# OUT_7SEG.net
KiCad netlist of a schematic drawn in EAGLE
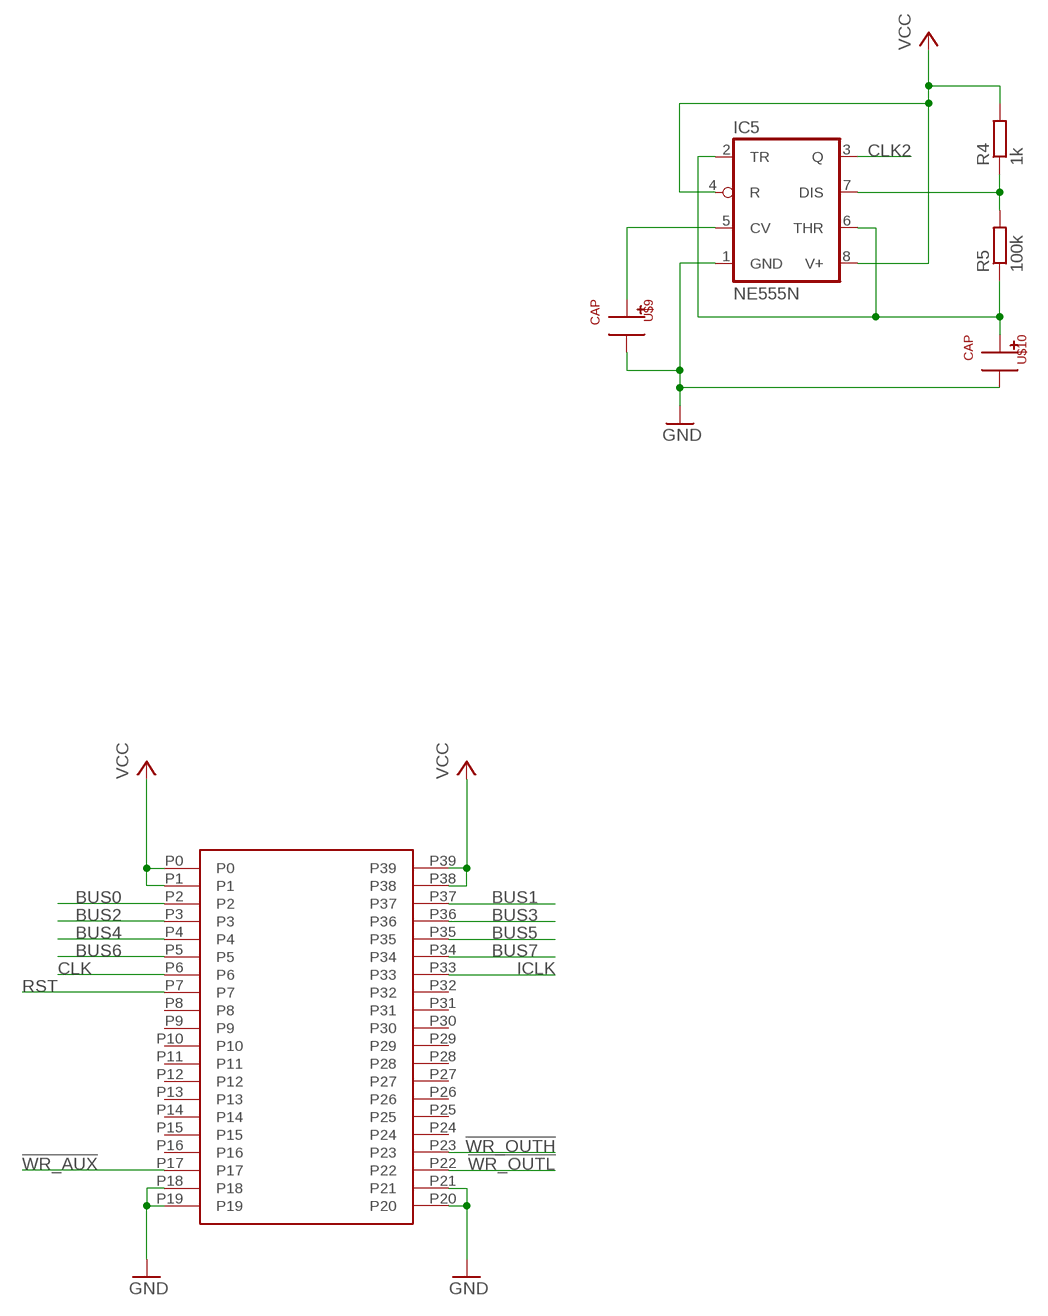
[diagram p0: schematic, sheet 1, part 1 of 2]
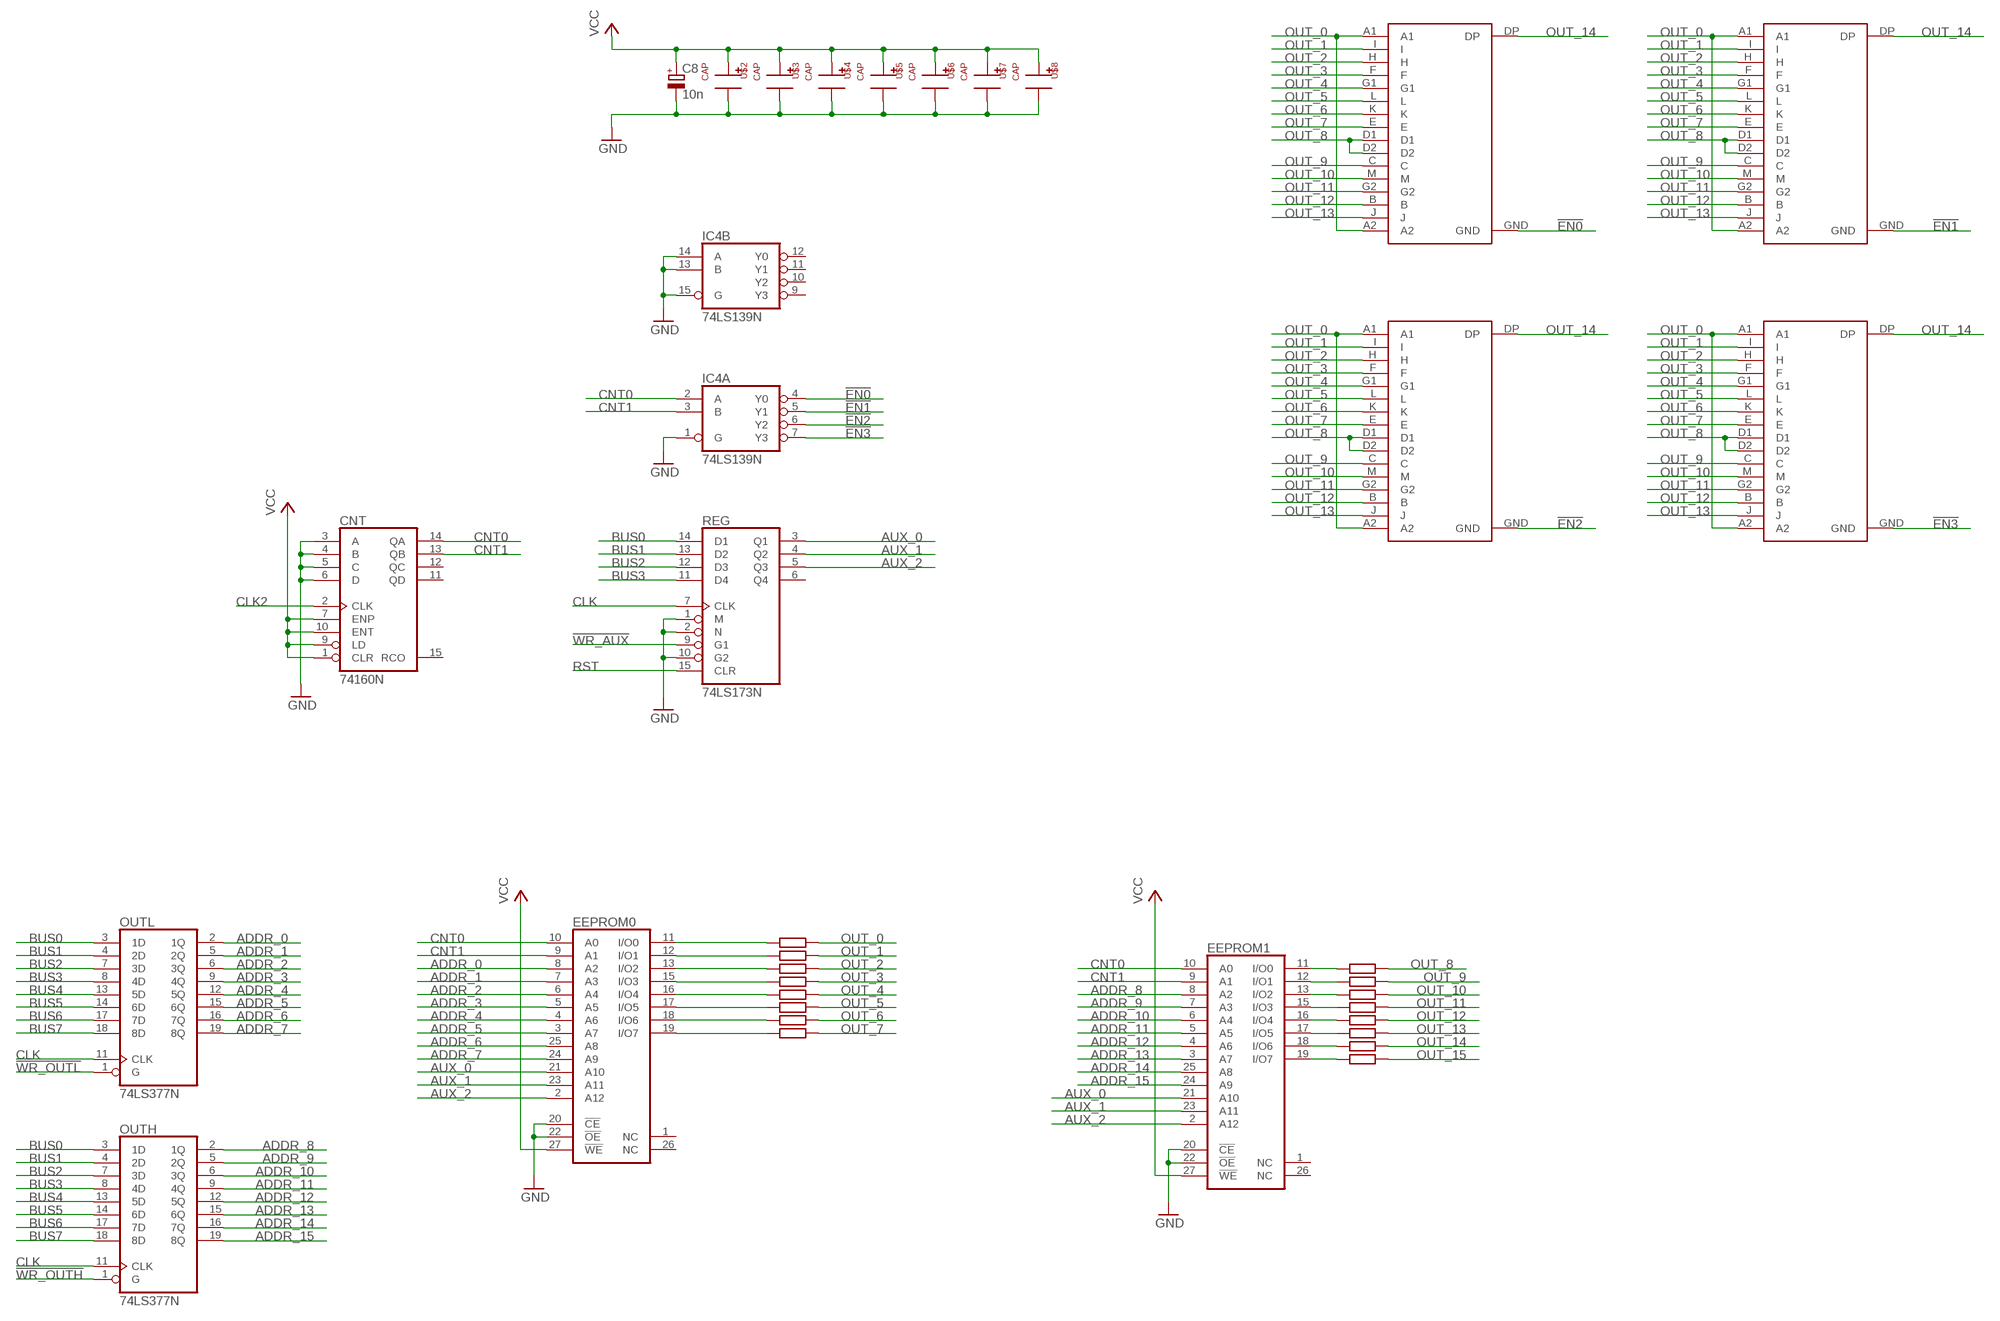
[diagram p1: schematic, sheet 1, part 2 of 2]

(export (version "E")
  (design (tool "Eeschema 10.0.6"))
  (components
    (comp (ref "C8")
      (value "10n")
      (footprint "eagle-import:E2,5-6E")
      (libsource (lib "eagle-import") (part "CPOL-EUE2,5-6E"))
    )
    (comp (ref "CNT")
      (value "74160N")
      (footprint "eagle-import:DIL16")
      (libsource (lib "eagle-import") (part "74160N"))
    )
    (comp (ref "DISP1")
      (value "16SEG")
      (footprint "eagle-import:16SEG")
      (libsource (lib "eagle-import") (part "16SEG"))
    )
    (comp (ref "DISP2")
      (value "16SEG")
      (footprint "eagle-import:16SEG")
      (libsource (lib "eagle-import") (part "16SEG"))
    )
    (comp (ref "DISP3")
      (value "16SEG")
      (footprint "eagle-import:16SEG")
      (libsource (lib "eagle-import") (part "16SEG"))
    )
    (comp (ref "DISP4")
      (value "16SEG")
      (footprint "eagle-import:16SEG")
      (libsource (lib "eagle-import") (part "16SEG"))
    )
    (comp (ref "EEPROM0")
      (value "78C64P")
      (footprint "eagle-import:DIL28-6")
      (libsource (lib "eagle-import") (part "78C64P"))
    )
    (comp (ref "EEPROM1")
      (value "78C64P")
      (footprint "eagle-import:DIL28-6")
      (libsource (lib "eagle-import") (part "78C64P"))
    )
    (comp (ref "IC4")
      (value "74LS139N")
      (footprint "eagle-import:DIL16")
      (libsource (lib "eagle-import") (part "74139NLS"))
    )
    (comp (ref "IC5")
      (value "NE555N")
      (footprint "eagle-import:DIL08")
      (libsource (lib "eagle-import") (part "555NNE"))
    )
    (comp (ref "OUTH")
      (value "74LS377N")
      (footprint "eagle-import:DIL20")
      (libsource (lib "eagle-import") (part "74377NLS"))
    )
    (comp (ref "OUTL")
      (value "74LS377N")
      (footprint "eagle-import:DIL20")
      (libsource (lib "eagle-import") (part "74377NLS"))
    )
    (comp (ref "R1")
      (value "330")
      (footprint "eagle-import:R0805")
      (libsource (lib "eagle-import") (part "R-EU_R0805"))
    )
    (comp (ref "R2")
      (value "330")
      (footprint "eagle-import:R0805")
      (libsource (lib "eagle-import") (part "R-EU_R0805"))
    )
    (comp (ref "R3")
      (value "330")
      (footprint "eagle-import:R0805")
      (libsource (lib "eagle-import") (part "R-EU_R0805"))
    )
    (comp (ref "R4")
      (value "1k")
      (footprint "eagle-import:0204_7")
      (libsource (lib "eagle-import") (part "R-EU_0204/7"))
    )
    (comp (ref "R5")
      (value "100k")
      (footprint "eagle-import:0204_7")
      (libsource (lib "eagle-import") (part "R-EU_0204/7"))
    )
    (comp (ref "R6")
      (value "330")
      (footprint "eagle-import:R0805")
      (libsource (lib "eagle-import") (part "R-EU_R0805"))
    )
    (comp (ref "R7")
      (value "330")
      (footprint "eagle-import:R0805")
      (libsource (lib "eagle-import") (part "R-EU_R0805"))
    )
    (comp (ref "R8")
      (value "330")
      (footprint "eagle-import:R0805")
      (libsource (lib "eagle-import") (part "R-EU_R0805"))
    )
    (comp (ref "R9")
      (value "330")
      (footprint "eagle-import:R0805")
      (libsource (lib "eagle-import") (part "R-EU_R0805"))
    )
    (comp (ref "R10")
      (value "330")
      (footprint "eagle-import:R0805")
      (libsource (lib "eagle-import") (part "R-EU_R0805"))
    )
    (comp (ref "R11")
      (value "330")
      (footprint "eagle-import:R0805")
      (libsource (lib "eagle-import") (part "R-EU_R0805"))
    )
    (comp (ref "R12")
      (value "330")
      (footprint "eagle-import:R0805")
      (libsource (lib "eagle-import") (part "R-EU_R0805"))
    )
    (comp (ref "R13")
      (value "330")
      (footprint "eagle-import:R0805")
      (libsource (lib "eagle-import") (part "R-EU_R0805"))
    )
    (comp (ref "R14")
      (value "330")
      (footprint "eagle-import:R0805")
      (libsource (lib "eagle-import") (part "R-EU_R0805"))
    )
    (comp (ref "R15")
      (value "330")
      (footprint "eagle-import:R0805")
      (libsource (lib "eagle-import") (part "R-EU_R0805"))
    )
    (comp (ref "R16")
      (value "330")
      (footprint "eagle-import:R0805")
      (libsource (lib "eagle-import") (part "R-EU_R0805"))
    )
    (comp (ref "R17")
      (value "330")
      (footprint "eagle-import:R0805")
      (libsource (lib "eagle-import") (part "R-EU_R0805"))
    )
    (comp (ref "R41")
      (value "330")
      (footprint "eagle-import:R0805")
      (libsource (lib "eagle-import") (part "R-EU_R0805"))
    )
    (comp (ref "REG")
      (value "74LS173N")
      (footprint "eagle-import:DIL16")
      (libsource (lib "eagle-import") (part "74173NLS"))
    )
    (comp (ref "U$1")
      (value "2X40")
      (footprint "eagle-import:2X40")
      (libsource (lib "eagle-import") (part "2X40"))
    )
    (comp (ref "U$2")
      (value "CAP")
      (footprint "eagle-import:CAP")
      (libsource (lib "eagle-import") (part "CAP"))
    )
    (comp (ref "U$3")
      (value "CAP")
      (footprint "eagle-import:CAP")
      (libsource (lib "eagle-import") (part "CAP"))
    )
    (comp (ref "U$4")
      (value "CAP")
      (footprint "eagle-import:CAP")
      (libsource (lib "eagle-import") (part "CAP"))
    )
    (comp (ref "U$5")
      (value "CAP")
      (footprint "eagle-import:CAP")
      (libsource (lib "eagle-import") (part "CAP"))
    )
    (comp (ref "U$6")
      (value "CAP")
      (footprint "eagle-import:CAP")
      (libsource (lib "eagle-import") (part "CAP"))
    )
    (comp (ref "U$7")
      (value "CAP")
      (footprint "eagle-import:CAP")
      (libsource (lib "eagle-import") (part "CAP"))
    )
    (comp (ref "U$8")
      (value "CAP")
      (footprint "eagle-import:CAP")
      (libsource (lib "eagle-import") (part "CAP"))
    )
    (comp (ref "U$9")
      (value "CAP")
      (footprint "eagle-import:CAP")
      (libsource (lib "eagle-import") (part "CAP"))
    )
    (comp (ref "U$10")
      (value "CAP")
      (footprint "eagle-import:CAP")
      (libsource (lib "eagle-import") (part "CAP"))
    )
  )
  (nets
    (net (code "1") (name "/ADDR_0") (class "Default")
      (node (ref "EEPROM0") (pin "8") (pinfunction "A2_8") (pintype "input"))
      (node (ref "OUTL") (pin "2") (pinfunction "1Q_2") (pintype "output"))
    )
    (net (code "2") (name "/ADDR_1") (class "Default")
      (node (ref "EEPROM0") (pin "7") (pinfunction "A3_7") (pintype "input"))
      (node (ref "OUTL") (pin "5") (pinfunction "2Q_5") (pintype "output"))
    )
    (net (code "3") (name "/ADDR_2") (class "Default")
      (node (ref "EEPROM0") (pin "6") (pinfunction "A4_6") (pintype "input"))
      (node (ref "OUTL") (pin "6") (pinfunction "3Q_6") (pintype "output"))
    )
    (net (code "4") (name "/ADDR_3") (class "Default")
      (node (ref "EEPROM0") (pin "5") (pinfunction "A5_5") (pintype "input"))
      (node (ref "OUTL") (pin "9") (pinfunction "4Q_9") (pintype "output"))
    )
    (net (code "5") (name "/ADDR_4") (class "Default")
      (node (ref "EEPROM0") (pin "4") (pinfunction "A6_4") (pintype "input"))
      (node (ref "OUTL") (pin "12") (pinfunction "5Q_12") (pintype "output"))
    )
    (net (code "6") (name "/ADDR_5") (class "Default")
      (node (ref "EEPROM0") (pin "3") (pinfunction "A7_3") (pintype "input"))
      (node (ref "OUTL") (pin "15") (pinfunction "6Q_15") (pintype "output"))
    )
    (net (code "7") (name "/ADDR_6") (class "Default")
      (node (ref "EEPROM0") (pin "25") (pinfunction "A8_25") (pintype "input"))
      (node (ref "OUTL") (pin "16") (pinfunction "7Q_16") (pintype "output"))
    )
    (net (code "8") (name "/ADDR_7") (class "Default")
      (node (ref "EEPROM0") (pin "24") (pinfunction "A9_24") (pintype "input"))
      (node (ref "OUTL") (pin "19") (pinfunction "8Q_19") (pintype "output"))
    )
    (net (code "9") (name "/ADDR_8") (class "Default")
      (node (ref "EEPROM1") (pin "8") (pinfunction "A2_8") (pintype "input"))
      (node (ref "OUTH") (pin "2") (pinfunction "1Q_2") (pintype "output"))
    )
    (net (code "10") (name "/ADDR_9") (class "Default")
      (node (ref "EEPROM1") (pin "7") (pinfunction "A3_7") (pintype "input"))
      (node (ref "OUTH") (pin "5") (pinfunction "2Q_5") (pintype "output"))
    )
    (net (code "11") (name "/ADDR_10") (class "Default")
      (node (ref "EEPROM1") (pin "6") (pinfunction "A4_6") (pintype "input"))
      (node (ref "OUTH") (pin "6") (pinfunction "3Q_6") (pintype "output"))
    )
    (net (code "12") (name "/ADDR_11") (class "Default")
      (node (ref "EEPROM1") (pin "5") (pinfunction "A5_5") (pintype "input"))
      (node (ref "OUTH") (pin "9") (pinfunction "4Q_9") (pintype "output"))
    )
    (net (code "13") (name "/ADDR_12") (class "Default")
      (node (ref "EEPROM1") (pin "4") (pinfunction "A6_4") (pintype "input"))
      (node (ref "OUTH") (pin "12") (pinfunction "5Q_12") (pintype "output"))
    )
    (net (code "14") (name "/ADDR_13") (class "Default")
      (node (ref "EEPROM1") (pin "3") (pinfunction "A7_3") (pintype "input"))
      (node (ref "OUTH") (pin "15") (pinfunction "6Q_15") (pintype "output"))
    )
    (net (code "15") (name "/ADDR_14") (class "Default")
      (node (ref "EEPROM1") (pin "25") (pinfunction "A8_25") (pintype "input"))
      (node (ref "OUTH") (pin "16") (pinfunction "7Q_16") (pintype "output"))
    )
    (net (code "16") (name "/ADDR_15") (class "Default")
      (node (ref "EEPROM1") (pin "24") (pinfunction "A9_24") (pintype "input"))
      (node (ref "OUTH") (pin "19") (pinfunction "8Q_19") (pintype "output"))
    )
    (net (code "17") (name "/AUX_0") (class "Default")
      (node (ref "EEPROM0") (pin "21") (pinfunction "A10_21") (pintype "input"))
      (node (ref "EEPROM1") (pin "21") (pinfunction "A10_21") (pintype "input"))
      (node (ref "REG") (pin "3") (pinfunction "Q1_3") (pintype "tri_state"))
    )
    (net (code "18") (name "/AUX_1") (class "Default")
      (node (ref "EEPROM0") (pin "23") (pinfunction "A11_23") (pintype "input"))
      (node (ref "EEPROM1") (pin "23") (pinfunction "A11_23") (pintype "input"))
      (node (ref "REG") (pin "4") (pinfunction "Q2_4") (pintype "tri_state"))
    )
    (net (code "19") (name "/AUX_2") (class "Default")
      (node (ref "EEPROM0") (pin "2") (pinfunction "A12_2") (pintype "input"))
      (node (ref "EEPROM1") (pin "2") (pinfunction "A12_2") (pintype "input"))
      (node (ref "REG") (pin "5") (pinfunction "Q3_5") (pintype "tri_state"))
    )
    (net (code "20") (name "/BUS0") (class "Default")
      (node (ref "OUTH") (pin "3") (pinfunction "1D_3") (pintype "input"))
      (node (ref "OUTL") (pin "3") (pinfunction "1D_3") (pintype "input"))
      (node (ref "REG") (pin "14") (pinfunction "D1_14") (pintype "input"))
      (node (ref "U$1") (pin "P2") (pinfunction "P2_P2") (pintype "bidirectional"))
    )
    (net (code "21") (name "/BUS1") (class "Default")
      (node (ref "OUTH") (pin "4") (pinfunction "2D_4") (pintype "input"))
      (node (ref "OUTL") (pin "4") (pinfunction "2D_4") (pintype "input"))
      (node (ref "REG") (pin "13") (pinfunction "D2_13") (pintype "input"))
      (node (ref "U$1") (pin "P37") (pinfunction "P37_P37") (pintype "bidirectional"))
    )
    (net (code "22") (name "/BUS2") (class "Default")
      (node (ref "OUTH") (pin "7") (pinfunction "3D_7") (pintype "input"))
      (node (ref "OUTL") (pin "7") (pinfunction "3D_7") (pintype "input"))
      (node (ref "REG") (pin "12") (pinfunction "D3_12") (pintype "input"))
      (node (ref "U$1") (pin "P3") (pinfunction "P3_P3") (pintype "bidirectional"))
    )
    (net (code "23") (name "/BUS3") (class "Default")
      (node (ref "OUTH") (pin "8") (pinfunction "4D_8") (pintype "input"))
      (node (ref "OUTL") (pin "8") (pinfunction "4D_8") (pintype "input"))
      (node (ref "REG") (pin "11") (pinfunction "D4_11") (pintype "input"))
      (node (ref "U$1") (pin "P36") (pinfunction "P36_P36") (pintype "bidirectional"))
    )
    (net (code "24") (name "/BUS4") (class "Default")
      (node (ref "OUTH") (pin "13") (pinfunction "5D_13") (pintype "input"))
      (node (ref "OUTL") (pin "13") (pinfunction "5D_13") (pintype "input"))
      (node (ref "U$1") (pin "P4") (pinfunction "P4_P4") (pintype "bidirectional"))
    )
    (net (code "25") (name "/BUS5") (class "Default")
      (node (ref "OUTH") (pin "14") (pinfunction "6D_14") (pintype "input"))
      (node (ref "OUTL") (pin "14") (pinfunction "6D_14") (pintype "input"))
      (node (ref "U$1") (pin "P35") (pinfunction "P35_P35") (pintype "bidirectional"))
    )
    (net (code "26") (name "/BUS6") (class "Default")
      (node (ref "OUTH") (pin "17") (pinfunction "7D_17") (pintype "input"))
      (node (ref "OUTL") (pin "17") (pinfunction "7D_17") (pintype "input"))
      (node (ref "U$1") (pin "P5") (pinfunction "P5_P5") (pintype "bidirectional"))
    )
    (net (code "27") (name "/BUS7") (class "Default")
      (node (ref "OUTH") (pin "18") (pinfunction "8D_18") (pintype "input"))
      (node (ref "OUTL") (pin "18") (pinfunction "8D_18") (pintype "input"))
      (node (ref "U$1") (pin "P34") (pinfunction "P34_P34") (pintype "bidirectional"))
    )
    (net (code "28") (name "/CLK") (class "Default")
      (node (ref "OUTH") (pin "11") (pinfunction "CLK_11") (pintype "input"))
      (node (ref "OUTL") (pin "11") (pinfunction "CLK_11") (pintype "input"))
      (node (ref "REG") (pin "7") (pinfunction "CLK_7") (pintype "input"))
      (node (ref "U$1") (pin "P6") (pinfunction "P6_P6") (pintype "bidirectional"))
    )
    (net (code "29") (name "/CLK2") (class "Default")
      (node (ref "CNT") (pin "2") (pinfunction "CLK_2") (pintype "input"))
      (node (ref "IC5") (pin "3") (pinfunction "Q_3") (pintype "output"))
    )
    (net (code "30") (name "/CNT0") (class "Default")
      (node (ref "CNT") (pin "14") (pinfunction "QA_14") (pintype "output"))
      (node (ref "EEPROM0") (pin "10") (pinfunction "A0_10") (pintype "input"))
      (node (ref "EEPROM1") (pin "10") (pinfunction "A0_10") (pintype "input"))
      (node (ref "IC4") (pin "2") (pinfunction "A_2") (pintype "input"))
    )
    (net (code "31") (name "/CNT1") (class "Default")
      (node (ref "CNT") (pin "13") (pinfunction "QB_13") (pintype "output"))
      (node (ref "EEPROM0") (pin "9") (pinfunction "A1_9") (pintype "input"))
      (node (ref "EEPROM1") (pin "9") (pinfunction "A1_9") (pintype "input"))
      (node (ref "IC4") (pin "3") (pinfunction "B_3") (pintype "input"))
    )
    (net (code "32") (name "/ICLK") (class "Default")
      (node (ref "U$1") (pin "P33") (pinfunction "P33_P33") (pintype "bidirectional"))
    )
    (net (code "33") (name "/OUT_0") (class "Default")
      (node (ref "DISP1") (pin "A1") (pinfunction "A1_A1") (pintype "bidirectional"))
      (node (ref "DISP1") (pin "A2") (pinfunction "A2_A2") (pintype "bidirectional"))
      (node (ref "DISP2") (pin "A1") (pinfunction "A1_A1") (pintype "bidirectional"))
      (node (ref "DISP2") (pin "A2") (pinfunction "A2_A2") (pintype "bidirectional"))
      (node (ref "DISP3") (pin "A1") (pinfunction "A1_A1") (pintype "bidirectional"))
      (node (ref "DISP3") (pin "A2") (pinfunction "A2_A2") (pintype "bidirectional"))
      (node (ref "DISP4") (pin "A1") (pinfunction "A1_A1") (pintype "bidirectional"))
      (node (ref "DISP4") (pin "A2") (pinfunction "A2_A2") (pintype "bidirectional"))
      (node (ref "R10") (pin "2") (pinfunction "2_2") (pintype "passive"))
    )
    (net (code "34") (name "/OUT_1") (class "Default")
      (node (ref "DISP1") (pin "I") (pinfunction "I_I") (pintype "bidirectional"))
      (node (ref "DISP2") (pin "I") (pinfunction "I_I") (pintype "bidirectional"))
      (node (ref "DISP3") (pin "I") (pinfunction "I_I") (pintype "bidirectional"))
      (node (ref "DISP4") (pin "I") (pinfunction "I_I") (pintype "bidirectional"))
      (node (ref "R11") (pin "2") (pinfunction "2_2") (pintype "passive"))
    )
    (net (code "35") (name "/OUT_2") (class "Default")
      (node (ref "DISP1") (pin "H") (pinfunction "H_H") (pintype "bidirectional"))
      (node (ref "DISP2") (pin "H") (pinfunction "H_H") (pintype "bidirectional"))
      (node (ref "DISP3") (pin "H") (pinfunction "H_H") (pintype "bidirectional"))
      (node (ref "DISP4") (pin "H") (pinfunction "H_H") (pintype "bidirectional"))
      (node (ref "R12") (pin "2") (pinfunction "2_2") (pintype "passive"))
    )
    (net (code "36") (name "/OUT_3") (class "Default")
      (node (ref "DISP1") (pin "F") (pinfunction "F_F") (pintype "bidirectional"))
      (node (ref "DISP2") (pin "F") (pinfunction "F_F") (pintype "bidirectional"))
      (node (ref "DISP3") (pin "F") (pinfunction "F_F") (pintype "bidirectional"))
      (node (ref "DISP4") (pin "F") (pinfunction "F_F") (pintype "bidirectional"))
      (node (ref "R13") (pin "2") (pinfunction "2_2") (pintype "passive"))
    )
    (net (code "37") (name "/OUT_4") (class "Default")
      (node (ref "DISP1") (pin "G1") (pinfunction "G1_G1") (pintype "bidirectional"))
      (node (ref "DISP2") (pin "G1") (pinfunction "G1_G1") (pintype "bidirectional"))
      (node (ref "DISP3") (pin "G1") (pinfunction "G1_G1") (pintype "bidirectional"))
      (node (ref "DISP4") (pin "G1") (pinfunction "G1_G1") (pintype "bidirectional"))
      (node (ref "R14") (pin "2") (pinfunction "2_2") (pintype "passive"))
    )
    (net (code "38") (name "/OUT_5") (class "Default")
      (node (ref "DISP1") (pin "L") (pinfunction "L_L") (pintype "bidirectional"))
      (node (ref "DISP2") (pin "L") (pinfunction "L_L") (pintype "bidirectional"))
      (node (ref "DISP3") (pin "L") (pinfunction "L_L") (pintype "bidirectional"))
      (node (ref "DISP4") (pin "L") (pinfunction "L_L") (pintype "bidirectional"))
      (node (ref "R16") (pin "2") (pinfunction "2_2") (pintype "passive"))
    )
    (net (code "39") (name "/OUT_6") (class "Default")
      (node (ref "DISP1") (pin "K") (pinfunction "K_K") (pintype "bidirectional"))
      (node (ref "DISP2") (pin "K") (pinfunction "K_K") (pintype "bidirectional"))
      (node (ref "DISP3") (pin "K") (pinfunction "K_K") (pintype "bidirectional"))
      (node (ref "DISP4") (pin "K") (pinfunction "K_K") (pintype "bidirectional"))
      (node (ref "R15") (pin "2") (pinfunction "2_2") (pintype "passive"))
    )
    (net (code "40") (name "/OUT_7") (class "Default")
      (node (ref "DISP1") (pin "E") (pinfunction "E_E") (pintype "bidirectional"))
      (node (ref "DISP2") (pin "E") (pinfunction "E_E") (pintype "bidirectional"))
      (node (ref "DISP3") (pin "E") (pinfunction "E_E") (pintype "bidirectional"))
      (node (ref "DISP4") (pin "E") (pinfunction "E_E") (pintype "bidirectional"))
      (node (ref "R17") (pin "2") (pinfunction "2_2") (pintype "passive"))
    )
    (net (code "41") (name "/OUT_8") (class "Default")
      (node (ref "DISP1") (pin "D1") (pinfunction "D1_D1") (pintype "bidirectional"))
      (node (ref "DISP1") (pin "D2") (pinfunction "D2_D2") (pintype "bidirectional"))
      (node (ref "DISP2") (pin "D1") (pinfunction "D1_D1") (pintype "bidirectional"))
      (node (ref "DISP2") (pin "D2") (pinfunction "D2_D2") (pintype "bidirectional"))
      (node (ref "DISP3") (pin "D1") (pinfunction "D1_D1") (pintype "bidirectional"))
      (node (ref "DISP3") (pin "D2") (pinfunction "D2_D2") (pintype "bidirectional"))
      (node (ref "DISP4") (pin "D1") (pinfunction "D1_D1") (pintype "bidirectional"))
      (node (ref "DISP4") (pin "D2") (pinfunction "D2_D2") (pintype "bidirectional"))
      (node (ref "R41") (pin "2") (pinfunction "2_2") (pintype "passive"))
    )
    (net (code "42") (name "/OUT_9") (class "Default")
      (node (ref "DISP1") (pin "C") (pinfunction "C_C") (pintype "bidirectional"))
      (node (ref "DISP2") (pin "C") (pinfunction "C_C") (pintype "bidirectional"))
      (node (ref "DISP3") (pin "C") (pinfunction "C_C") (pintype "bidirectional"))
      (node (ref "DISP4") (pin "C") (pinfunction "C_C") (pintype "bidirectional"))
      (node (ref "R1") (pin "2") (pinfunction "2_2") (pintype "passive"))
    )
    (net (code "43") (name "/OUT_10") (class "Default")
      (node (ref "DISP1") (pin "M") (pinfunction "M_M") (pintype "bidirectional"))
      (node (ref "DISP2") (pin "M") (pinfunction "M_M") (pintype "bidirectional"))
      (node (ref "DISP3") (pin "M") (pinfunction "M_M") (pintype "bidirectional"))
      (node (ref "DISP4") (pin "M") (pinfunction "M_M") (pintype "bidirectional"))
      (node (ref "R2") (pin "2") (pinfunction "2_2") (pintype "passive"))
    )
    (net (code "44") (name "/OUT_11") (class "Default")
      (node (ref "DISP1") (pin "G2") (pinfunction "G2_G2") (pintype "bidirectional"))
      (node (ref "DISP2") (pin "G2") (pinfunction "G2_G2") (pintype "bidirectional"))
      (node (ref "DISP3") (pin "G2") (pinfunction "G2_G2") (pintype "bidirectional"))
      (node (ref "DISP4") (pin "G2") (pinfunction "G2_G2") (pintype "bidirectional"))
      (node (ref "R3") (pin "2") (pinfunction "2_2") (pintype "passive"))
    )
    (net (code "45") (name "/OUT_12") (class "Default")
      (node (ref "DISP1") (pin "B") (pinfunction "B_B") (pintype "bidirectional"))
      (node (ref "DISP2") (pin "B") (pinfunction "B_B") (pintype "bidirectional"))
      (node (ref "DISP3") (pin "B") (pinfunction "B_B") (pintype "bidirectional"))
      (node (ref "DISP4") (pin "B") (pinfunction "B_B") (pintype "bidirectional"))
      (node (ref "R6") (pin "2") (pinfunction "2_2") (pintype "passive"))
    )
    (net (code "46") (name "/OUT_13") (class "Default")
      (node (ref "DISP1") (pin "J") (pinfunction "J_J") (pintype "bidirectional"))
      (node (ref "DISP2") (pin "J") (pinfunction "J_J") (pintype "bidirectional"))
      (node (ref "DISP3") (pin "J") (pinfunction "J_J") (pintype "bidirectional"))
      (node (ref "DISP4") (pin "J") (pinfunction "J_J") (pintype "bidirectional"))
      (node (ref "R7") (pin "2") (pinfunction "2_2") (pintype "passive"))
    )
    (net (code "47") (name "/OUT_14") (class "Default")
      (node (ref "DISP1") (pin "DP") (pinfunction "DP_DP") (pintype "bidirectional"))
      (node (ref "DISP2") (pin "DP") (pinfunction "DP_DP") (pintype "bidirectional"))
      (node (ref "DISP3") (pin "DP") (pinfunction "DP_DP") (pintype "bidirectional"))
      (node (ref "DISP4") (pin "DP") (pinfunction "DP_DP") (pintype "bidirectional"))
      (node (ref "R8") (pin "2") (pinfunction "2_2") (pintype "passive"))
    )
    (net (code "48") (name "/OUT_15") (class "Default")
      (node (ref "R9") (pin "2") (pinfunction "2_2") (pintype "passive"))
    )
    (net (code "49") (name "/RST") (class "Default")
      (node (ref "REG") (pin "15") (pinfunction "CLR_15") (pintype "input"))
      (node (ref "U$1") (pin "P7") (pinfunction "P7_P7") (pintype "bidirectional"))
    )
    (net (code "50") (name "/~{EN0}") (class "Default")
      (node (ref "DISP1") (pin "GND") (pinfunction "GND_GND") (pintype "bidirectional"))
      (node (ref "IC4") (pin "4") (pinfunction "Y0_4") (pintype "output"))
    )
    (net (code "51") (name "/~{EN1}") (class "Default")
      (node (ref "DISP2") (pin "GND") (pinfunction "GND_GND") (pintype "bidirectional"))
      (node (ref "IC4") (pin "5") (pinfunction "Y1_5") (pintype "output"))
    )
    (net (code "52") (name "/~{EN2}") (class "Default")
      (node (ref "DISP3") (pin "GND") (pinfunction "GND_GND") (pintype "bidirectional"))
      (node (ref "IC4") (pin "6") (pinfunction "Y2_6") (pintype "output"))
    )
    (net (code "53") (name "/~{EN3}") (class "Default")
      (node (ref "DISP4") (pin "GND") (pinfunction "GND_GND") (pintype "bidirectional"))
      (node (ref "IC4") (pin "7") (pinfunction "Y3_7") (pintype "output"))
    )
    (net (code "54") (name "/~{WR_AUX}") (class "Default")
      (node (ref "REG") (pin "9") (pinfunction "G1_9") (pintype "input"))
      (node (ref "U$1") (pin "P17") (pinfunction "P17_P17") (pintype "bidirectional"))
    )
    (net (code "55") (name "/~{WR_OUTH}") (class "Default")
      (node (ref "OUTH") (pin "1") (pinfunction "G_1") (pintype "input"))
      (node (ref "U$1") (pin "P23") (pinfunction "P23_P23") (pintype "bidirectional"))
    )
    (net (code "56") (name "/~{WR_OUTL}") (class "Default")
      (node (ref "OUTL") (pin "1") (pinfunction "G_1") (pintype "input"))
      (node (ref "U$1") (pin "P22") (pinfunction "P22_P22") (pintype "bidirectional"))
    )
    (net (code "57") (name "GND") (class "Default")
      (node (ref "C8") (pin "-") (pinfunction "-_-") (pintype "passive"))
      (node (ref "CNT") (pin "3") (pinfunction "A_3") (pintype "input"))
      (node (ref "CNT") (pin "4") (pinfunction "B_4") (pintype "input"))
      (node (ref "CNT") (pin "5") (pinfunction "C_5") (pintype "input"))
      (node (ref "CNT") (pin "6") (pinfunction "D_6") (pintype "input"))
      (node (ref "EEPROM0") (pin "20") (pinfunction "~{CE}_20") (pintype "input"))
      (node (ref "EEPROM0") (pin "22") (pinfunction "~{OE}_22") (pintype "input"))
      (node (ref "EEPROM1") (pin "20") (pinfunction "~{CE}_20") (pintype "input"))
      (node (ref "EEPROM1") (pin "22") (pinfunction "~{OE}_22") (pintype "input"))
      (node (ref "IC4") (pin "1") (pinfunction "G_1") (pintype "input"))
      (node (ref "IC4") (pin "13") (pinfunction "B_13") (pintype "input"))
      (node (ref "IC4") (pin "14") (pinfunction "A_14") (pintype "input"))
      (node (ref "IC4") (pin "15") (pinfunction "G_15") (pintype "input"))
      (node (ref "IC5") (pin "1") (pinfunction "GND_1") (pintype "power_in"))
      (node (ref "REG") (pin "1") (pinfunction "M_1") (pintype "input"))
      (node (ref "REG") (pin "10") (pinfunction "G2_10") (pintype "input"))
      (node (ref "REG") (pin "2") (pinfunction "N_2") (pintype "input"))
      (node (ref "U$1") (pin "P18") (pinfunction "P18_P18") (pintype "bidirectional"))
      (node (ref "U$1") (pin "P19") (pinfunction "P19_P19") (pintype "bidirectional"))
      (node (ref "U$1") (pin "P20") (pinfunction "P20_P20") (pintype "bidirectional"))
      (node (ref "U$1") (pin "P21") (pinfunction "P21_P21") (pintype "bidirectional"))
      (node (ref "U$10") (pin "P-") (pinfunction "P-_P-") (pintype "bidirectional"))
      (node (ref "U$2") (pin "P-") (pinfunction "P-_P-") (pintype "bidirectional"))
      (node (ref "U$3") (pin "P-") (pinfunction "P-_P-") (pintype "bidirectional"))
      (node (ref "U$4") (pin "P-") (pinfunction "P-_P-") (pintype "bidirectional"))
      (node (ref "U$5") (pin "P-") (pinfunction "P-_P-") (pintype "bidirectional"))
      (node (ref "U$6") (pin "P-") (pinfunction "P-_P-") (pintype "bidirectional"))
      (node (ref "U$7") (pin "P-") (pinfunction "P-_P-") (pintype "bidirectional"))
      (node (ref "U$8") (pin "P-") (pinfunction "P-_P-") (pintype "bidirectional"))
      (node (ref "U$9") (pin "P-") (pinfunction "P-_P-") (pintype "bidirectional"))
    )
    (net (code "58") (name "Net-(EEPROM0A-I{slash}O0)") (class "Default")
      (node (ref "EEPROM0") (pin "11") (pinfunction "I/O0_11") (pintype "bidirectional"))
      (node (ref "R10") (pin "1") (pinfunction "1_1") (pintype "passive"))
    )
    (net (code "59") (name "Net-(EEPROM0A-I{slash}O1)") (class "Default")
      (node (ref "EEPROM0") (pin "12") (pinfunction "I/O1_12") (pintype "bidirectional"))
      (node (ref "R11") (pin "1") (pinfunction "1_1") (pintype "passive"))
    )
    (net (code "60") (name "Net-(EEPROM0A-I{slash}O2)") (class "Default")
      (node (ref "EEPROM0") (pin "13") (pinfunction "I/O2_13") (pintype "bidirectional"))
      (node (ref "R12") (pin "1") (pinfunction "1_1") (pintype "passive"))
    )
    (net (code "61") (name "Net-(EEPROM0A-I{slash}O3)") (class "Default")
      (node (ref "EEPROM0") (pin "15") (pinfunction "I/O3_15") (pintype "bidirectional"))
      (node (ref "R13") (pin "1") (pinfunction "1_1") (pintype "passive"))
    )
    (net (code "62") (name "Net-(EEPROM0A-I{slash}O4)") (class "Default")
      (node (ref "EEPROM0") (pin "16") (pinfunction "I/O4_16") (pintype "bidirectional"))
      (node (ref "R14") (pin "1") (pinfunction "1_1") (pintype "passive"))
    )
    (net (code "63") (name "Net-(EEPROM0A-I{slash}O5)") (class "Default")
      (node (ref "EEPROM0") (pin "17") (pinfunction "I/O5_17") (pintype "bidirectional"))
      (node (ref "R16") (pin "1") (pinfunction "1_1") (pintype "passive"))
    )
    (net (code "64") (name "Net-(EEPROM0A-I{slash}O6)") (class "Default")
      (node (ref "EEPROM0") (pin "18") (pinfunction "I/O6_18") (pintype "bidirectional"))
      (node (ref "R15") (pin "1") (pinfunction "1_1") (pintype "passive"))
    )
    (net (code "65") (name "Net-(EEPROM0A-I{slash}O7)") (class "Default")
      (node (ref "EEPROM0") (pin "19") (pinfunction "I/O7_19") (pintype "bidirectional"))
      (node (ref "R17") (pin "1") (pinfunction "1_1") (pintype "passive"))
    )
    (net (code "66") (name "Net-(EEPROM1A-I{slash}O0)") (class "Default")
      (node (ref "EEPROM1") (pin "11") (pinfunction "I/O0_11") (pintype "bidirectional"))
      (node (ref "R41") (pin "1") (pinfunction "1_1") (pintype "passive"))
    )
    (net (code "67") (name "Net-(EEPROM1A-I{slash}O1)") (class "Default")
      (node (ref "EEPROM1") (pin "12") (pinfunction "I/O1_12") (pintype "bidirectional"))
      (node (ref "R1") (pin "1") (pinfunction "1_1") (pintype "passive"))
    )
    (net (code "68") (name "Net-(EEPROM1A-I{slash}O2)") (class "Default")
      (node (ref "EEPROM1") (pin "13") (pinfunction "I/O2_13") (pintype "bidirectional"))
      (node (ref "R2") (pin "1") (pinfunction "1_1") (pintype "passive"))
    )
    (net (code "69") (name "Net-(EEPROM1A-I{slash}O3)") (class "Default")
      (node (ref "EEPROM1") (pin "15") (pinfunction "I/O3_15") (pintype "bidirectional"))
      (node (ref "R3") (pin "1") (pinfunction "1_1") (pintype "passive"))
    )
    (net (code "70") (name "Net-(EEPROM1A-I{slash}O4)") (class "Default")
      (node (ref "EEPROM1") (pin "16") (pinfunction "I/O4_16") (pintype "bidirectional"))
      (node (ref "R6") (pin "1") (pinfunction "1_1") (pintype "passive"))
    )
    (net (code "71") (name "Net-(EEPROM1A-I{slash}O5)") (class "Default")
      (node (ref "EEPROM1") (pin "17") (pinfunction "I/O5_17") (pintype "bidirectional"))
      (node (ref "R7") (pin "1") (pinfunction "1_1") (pintype "passive"))
    )
    (net (code "72") (name "Net-(EEPROM1A-I{slash}O6)") (class "Default")
      (node (ref "EEPROM1") (pin "18") (pinfunction "I/O6_18") (pintype "bidirectional"))
      (node (ref "R8") (pin "1") (pinfunction "1_1") (pintype "passive"))
    )
    (net (code "73") (name "Net-(EEPROM1A-I{slash}O7)") (class "Default")
      (node (ref "EEPROM1") (pin "19") (pinfunction "I/O7_19") (pintype "bidirectional"))
      (node (ref "R9") (pin "1") (pinfunction "1_1") (pintype "passive"))
    )
    (net (code "74") (name "Net-(IC5-CV)") (class "Default")
      (node (ref "IC5") (pin "5") (pinfunction "CV_5") (pintype "input"))
      (node (ref "U$9") (pin "P+") (pinfunction "P+_P+") (pintype "bidirectional"))
    )
    (net (code "75") (name "Net-(IC5-DIS)") (class "Default")
      (node (ref "IC5") (pin "7") (pinfunction "DIS_7") (pintype "input"))
      (node (ref "R4") (pin "1") (pinfunction "1_1") (pintype "passive"))
      (node (ref "R5") (pin "2") (pinfunction "2_2") (pintype "passive"))
    )
    (net (code "76") (name "Net-(IC5-THR)") (class "Default")
      (node (ref "IC5") (pin "2") (pinfunction "TR_2") (pintype "input"))
      (node (ref "IC5") (pin "6") (pinfunction "THR_6") (pintype "input"))
      (node (ref "R5") (pin "1") (pinfunction "1_1") (pintype "passive"))
      (node (ref "U$10") (pin "P+") (pinfunction "P+_P+") (pintype "bidirectional"))
    )
    (net (code "77") (name "VCC") (class "Default")
      (node (ref "C8") (pin "+") (pinfunction "+_+") (pintype "passive"))
      (node (ref "CNT") (pin "1") (pinfunction "CLR_1") (pintype "input"))
      (node (ref "CNT") (pin "10") (pinfunction "ENT_10") (pintype "input"))
      (node (ref "CNT") (pin "7") (pinfunction "ENP_7") (pintype "input"))
      (node (ref "CNT") (pin "9") (pinfunction "LD_9") (pintype "input"))
      (node (ref "EEPROM0") (pin "27") (pinfunction "~{WE}_27") (pintype "input"))
      (node (ref "EEPROM1") (pin "27") (pinfunction "~{WE}_27") (pintype "input"))
      (node (ref "IC5") (pin "4") (pinfunction "R_4") (pintype "input"))
      (node (ref "IC5") (pin "8") (pinfunction "V+_8") (pintype "power_in"))
      (node (ref "R4") (pin "2") (pinfunction "2_2") (pintype "passive"))
      (node (ref "U$1") (pin "P0") (pinfunction "P0_P0") (pintype "bidirectional"))
      (node (ref "U$1") (pin "P1") (pinfunction "P1_P1") (pintype "bidirectional"))
      (node (ref "U$1") (pin "P38") (pinfunction "P38_P38") (pintype "bidirectional"))
      (node (ref "U$1") (pin "P39") (pinfunction "P39_P39") (pintype "bidirectional"))
      (node (ref "U$2") (pin "P+") (pinfunction "P+_P+") (pintype "bidirectional"))
      (node (ref "U$3") (pin "P+") (pinfunction "P+_P+") (pintype "bidirectional"))
      (node (ref "U$4") (pin "P+") (pinfunction "P+_P+") (pintype "bidirectional"))
      (node (ref "U$5") (pin "P+") (pinfunction "P+_P+") (pintype "bidirectional"))
      (node (ref "U$6") (pin "P+") (pinfunction "P+_P+") (pintype "bidirectional"))
      (node (ref "U$7") (pin "P+") (pinfunction "P+_P+") (pintype "bidirectional"))
      (node (ref "U$8") (pin "P+") (pinfunction "P+_P+") (pintype "bidirectional"))
    )
    (net (code "78") (name "unconnected-(CNTA-QC-Pad12)") (class "Default")
      (node (ref "CNT") (pin "12") (pinfunction "QC_12") (pintype "output"))
    )
    (net (code "79") (name "unconnected-(CNTA-QD-Pad11)") (class "Default")
      (node (ref "CNT") (pin "11") (pinfunction "QD_11") (pintype "output"))
    )
    (net (code "80") (name "unconnected-(CNTA-RCO-Pad15)") (class "Default")
      (node (ref "CNT") (pin "15") (pinfunction "RCO_15") (pintype "output"))
    )
    (net (code "81") (name "unconnected-(EEPROM0A-NC-Pad1)") (class "Default")
      (node (ref "EEPROM0") (pin "1") (pinfunction "NC_1") (pintype "no_connect"))
    )
    (net (code "82") (name "unconnected-(EEPROM0A-NC-Pad26)") (class "Default")
      (node (ref "EEPROM0") (pin "26") (pinfunction "NC_26") (pintype "no_connect"))
    )
    (net (code "83") (name "unconnected-(EEPROM1A-NC-Pad1)") (class "Default")
      (node (ref "EEPROM1") (pin "1") (pinfunction "NC_1") (pintype "no_connect"))
    )
    (net (code "84") (name "unconnected-(EEPROM1A-NC-Pad26)") (class "Default")
      (node (ref "EEPROM1") (pin "26") (pinfunction "NC_26") (pintype "no_connect"))
    )
    (net (code "85") (name "unconnected-(IC4B-Y0-Pad12)") (class "Default")
      (node (ref "IC4") (pin "12") (pinfunction "Y0_12") (pintype "output"))
    )
    (net (code "86") (name "unconnected-(IC4B-Y1-Pad11)") (class "Default")
      (node (ref "IC4") (pin "11") (pinfunction "Y1_11") (pintype "output"))
    )
    (net (code "87") (name "unconnected-(IC4B-Y2-Pad10)") (class "Default")
      (node (ref "IC4") (pin "10") (pinfunction "Y2_10") (pintype "output"))
    )
    (net (code "88") (name "unconnected-(IC4B-Y3-Pad9)") (class "Default")
      (node (ref "IC4") (pin "9") (pinfunction "Y3_9") (pintype "output"))
    )
    (net (code "89") (name "unconnected-(REGA-Q4-Pad6)") (class "Default")
      (node (ref "REG") (pin "6") (pinfunction "Q4_6") (pintype "tri_state"))
    )
    (net (code "90") (name "unconnected-(U$1-PadP8)") (class "Default")
      (node (ref "U$1") (pin "P8") (pinfunction "P8_P8") (pintype "bidirectional"))
    )
    (net (code "91") (name "unconnected-(U$1-PadP9)") (class "Default")
      (node (ref "U$1") (pin "P9") (pinfunction "P9_P9") (pintype "bidirectional"))
    )
    (net (code "92") (name "unconnected-(U$1-PadP10)") (class "Default")
      (node (ref "U$1") (pin "P10") (pinfunction "P10_P10") (pintype "bidirectional"))
    )
    (net (code "93") (name "unconnected-(U$1-PadP11)") (class "Default")
      (node (ref "U$1") (pin "P11") (pinfunction "P11_P11") (pintype "bidirectional"))
    )
    (net (code "94") (name "unconnected-(U$1-PadP12)") (class "Default")
      (node (ref "U$1") (pin "P12") (pinfunction "P12_P12") (pintype "bidirectional"))
    )
    (net (code "95") (name "unconnected-(U$1-PadP13)") (class "Default")
      (node (ref "U$1") (pin "P13") (pinfunction "P13_P13") (pintype "bidirectional"))
    )
    (net (code "96") (name "unconnected-(U$1-PadP14)") (class "Default")
      (node (ref "U$1") (pin "P14") (pinfunction "P14_P14") (pintype "bidirectional"))
    )
    (net (code "97") (name "unconnected-(U$1-PadP15)") (class "Default")
      (node (ref "U$1") (pin "P15") (pinfunction "P15_P15") (pintype "bidirectional"))
    )
    (net (code "98") (name "unconnected-(U$1-PadP16)") (class "Default")
      (node (ref "U$1") (pin "P16") (pinfunction "P16_P16") (pintype "bidirectional"))
    )
    (net (code "99") (name "unconnected-(U$1-PadP24)") (class "Default")
      (node (ref "U$1") (pin "P24") (pinfunction "P24_P24") (pintype "bidirectional"))
    )
    (net (code "100") (name "unconnected-(U$1-PadP25)") (class "Default")
      (node (ref "U$1") (pin "P25") (pinfunction "P25_P25") (pintype "bidirectional"))
    )
    (net (code "101") (name "unconnected-(U$1-PadP26)") (class "Default")
      (node (ref "U$1") (pin "P26") (pinfunction "P26_P26") (pintype "bidirectional"))
    )
    (net (code "102") (name "unconnected-(U$1-PadP27)") (class "Default")
      (node (ref "U$1") (pin "P27") (pinfunction "P27_P27") (pintype "bidirectional"))
    )
    (net (code "103") (name "unconnected-(U$1-PadP28)") (class "Default")
      (node (ref "U$1") (pin "P28") (pinfunction "P28_P28") (pintype "bidirectional"))
    )
    (net (code "104") (name "unconnected-(U$1-PadP29)") (class "Default")
      (node (ref "U$1") (pin "P29") (pinfunction "P29_P29") (pintype "bidirectional"))
    )
    (net (code "105") (name "unconnected-(U$1-PadP30)") (class "Default")
      (node (ref "U$1") (pin "P30") (pinfunction "P30_P30") (pintype "bidirectional"))
    )
    (net (code "106") (name "unconnected-(U$1-PadP31)") (class "Default")
      (node (ref "U$1") (pin "P31") (pinfunction "P31_P31") (pintype "bidirectional"))
    )
    (net (code "107") (name "unconnected-(U$1-PadP32)") (class "Default")
      (node (ref "U$1") (pin "P32") (pinfunction "P32_P32") (pintype "bidirectional"))
    )
  )
)
